# Sheet1.net
KiCad netlist of a schematic drawn in Altium Designer
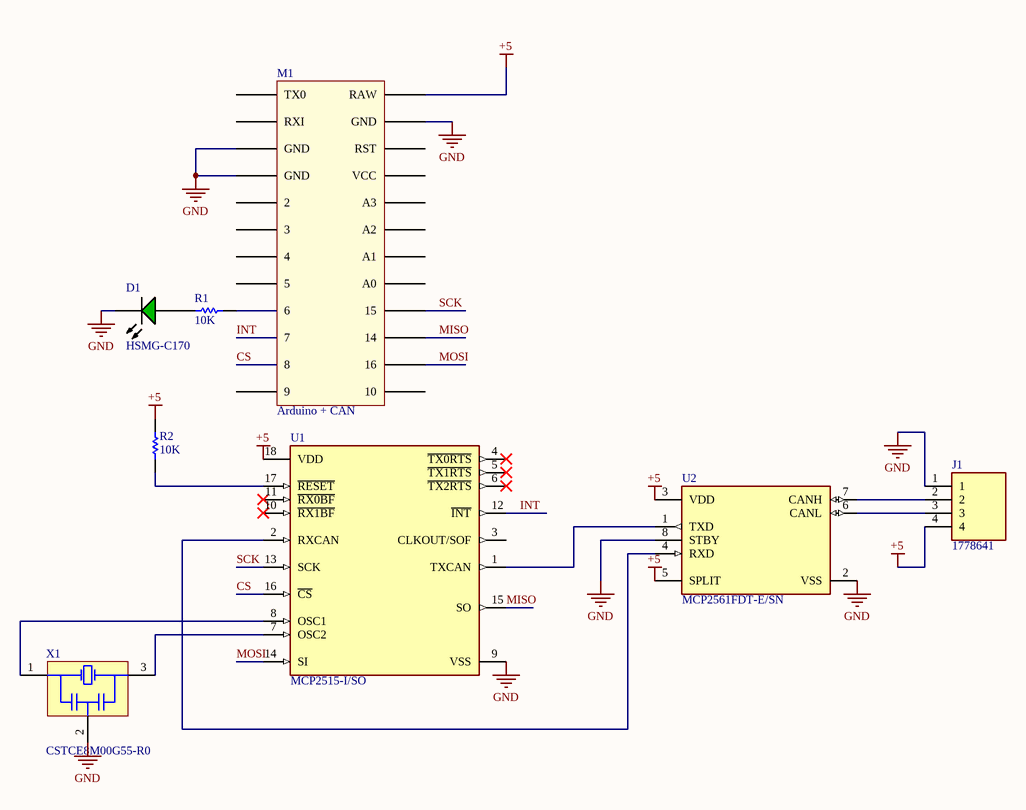
[diagram p0: Sheet1.SchDoc]

(export (version "E")
  (design (tool "Eeschema 10.0.6"))
  (components
    (comp (ref "D1")
      (value "HSMG-C170")
      (footprint "AVAG-HSMX-C170_V")
      (description "Chip LED, Green, 2.2 V, -40 to 85 degC, 2-Pin SMD, Pb-Free, Tape and Reel")
      (fields (field (name "MANUFACTURER") "Avago"))
      (libsource (lib "Altium Content Vault") (part "LED_GREEN_A1K2-2"))
    )
    (comp (ref "J1")
      (value "1778641")
      (footprint "SHDRRA4W60P0X250_1X4_1170X750X510P")
      (fields (field (name "MOUSER PART NUMBER") "651-1778641"))
      (libsource (lib "PTSM") (part "1778641"))
    )
    (comp (ref "M1")
      (value "Arduino + CAN")
      (footprint "PCBComponent_1")
      (description "Arduino Pro Micro + CAN Shield")
      (libsource (lib "Arduino") (part "Arduino"))
    )
    (comp (ref "R1")
      (value "10K")
      (footprint "RESC2013X50X30LL20T20")
      (fields (field (name "MANUFACTURER") "Vishay Dale") (field (name "PART NUMBER") "CRCW08050000Z0EA"))
      (libsource (lib "Altium Content Vault") (part "RES"))
    )
    (comp (ref "R2")
      (value "10K")
      (footprint "RESC2013X50X30LL20T20")
      (fields (field (name "MANUFACTURER") "Vishay Dale") (field (name "PART NUMBER") "CRCW08050000Z0EA"))
      (libsource (lib "Altium Content Vault") (part "RES"))
    )
    (comp (ref "U1")
      (value "MCP2515-I/SO")
      (footprint "FP-C04-051-MFG")
      (description "IC CAN CONTROLLER W/SPI 18SOIC")
      (fields
        (field (name "MANUFACTURER") "Microchip")
        (field (name "OCTOPART") "https://octopart.com/mcp2515-i%2Fso-microchip-430187")
      )
      (libsource (lib "Altium Content Vault") (part "1c78ea6ff576bac94664e2637e1b479"))
    )
    (comp (ref "U2")
      (value "MCP2561FDT-E/SN")
      (footprint "FP-C04-057-SN-MFG")
      (description "IC TRANSCEIVER 1/1 8SOIC")
      (libsource (lib "Altium Content Vault") (part "d629fcaead47a253bf8bf7df247dcfa"))
    )
    (comp (ref "X1")
      (value "CSTCE8M00G55-R0")
      (footprint "MURA-CSTCE_G_A-3_V")
      (description "Ceramic Resonator, 8 MHz, +/- 0.5%, -20 to 80 degC, 3-Pin SMD, RoHS, Tape and Reel")
      (fields (field (name "TOLERANCE") "0.5%") (field (name "MANUFACTURER") "Murata"))
      (libsource (lib "Altium Content Vault") (part "MURA-CSTCE_G_A-3"))
    )
  )
  (nets
    (net (code "1") (name "+5") (class "Default")
      (node (ref "J1") (pin "4") (pinfunction "4_4") (pintype "passive"))
      (node (ref "M1") (pin "24") (pinfunction "RAW_24") (pintype "passive"))
      (node (ref "R2") (pin "2") (pinfunction "2_2") (pintype "passive"))
      (node (ref "U1") (pin "18") (pinfunction "VDD_18") (pintype "power_in"))
      (node (ref "U2") (pin "3") (pinfunction "VDD_3") (pintype "power_in"))
      (node (ref "U2") (pin "5") (pinfunction "SPLIT_5") (pintype "passive"))
    )
    (net (code "2") (name "/CS") (class "Default")
      (node (ref "M1") (pin "11") (pinfunction "8_11") (pintype "passive"))
      (node (ref "U1") (pin "16") (pinfunction "~{CS}_16") (pintype "input"))
    )
    (net (code "3") (name "/INT") (class "Default")
      (node (ref "M1") (pin "10") (pinfunction "7_10") (pintype "passive"))
      (node (ref "U1") (pin "12") (pinfunction "~{INT}_12") (pintype "output"))
    )
    (net (code "4") (name "/MISO") (class "Default")
      (node (ref "M1") (pin "15") (pinfunction "14_15") (pintype "passive"))
      (node (ref "U1") (pin "15") (pinfunction "SO_15") (pintype "output"))
    )
    (net (code "5") (name "/MOSI") (class "Default")
      (node (ref "M1") (pin "14") (pinfunction "16_14") (pintype "passive"))
      (node (ref "U1") (pin "14") (pinfunction "SI_14") (pintype "input"))
    )
    (net (code "6") (name "/SCK") (class "Default")
      (node (ref "M1") (pin "16") (pinfunction "15_16") (pintype "passive"))
      (node (ref "U1") (pin "13") (pinfunction "SCK_13") (pintype "input"))
    )
    (net (code "7") (name "GND") (class "Default")
      (node (ref "D1") (pin "2") (pinfunction "K_2") (pintype "passive"))
      (node (ref "J1") (pin "1") (pinfunction "1_1") (pintype "passive"))
      (node (ref "M1") (pin "23") (pinfunction "GND_23") (pintype "passive"))
      (node (ref "M1") (pin "3") (pinfunction "GND_3") (pintype "passive"))
      (node (ref "M1") (pin "4") (pinfunction "GND_4") (pintype "passive"))
      (node (ref "U1") (pin "9") (pinfunction "VSS_9") (pintype "power_in"))
      (node (ref "U2") (pin "2") (pinfunction "VSS_2") (pintype "power_in"))
      (node (ref "U2") (pin "8") (pinfunction "STBY_8") (pintype "passive"))
      (node (ref "X1") (pin "2") (pinfunction "GND_2") (pintype "power_in"))
    )
    (net (code "8") (name "Net-(D1-A)") (class "Default")
      (node (ref "D1") (pin "1") (pinfunction "A_1") (pintype "passive"))
      (node (ref "R1") (pin "2") (pinfunction "2_2") (pintype "passive"))
    )
    (net (code "9") (name "Net-(M1-6)") (class "Default")
      (node (ref "M1") (pin "9") (pinfunction "6_9") (pintype "passive"))
      (node (ref "R1") (pin "1") (pinfunction "1_1") (pintype "passive"))
    )
    (net (code "10") (name "Net-(U1-OSC1)") (class "Default")
      (node (ref "U1") (pin "8") (pinfunction "OSC1_8") (pintype "input"))
      (node (ref "X1") (pin "1") (pinfunction "X1_1") (pintype "passive"))
    )
    (net (code "11") (name "Net-(U1-OSC2)") (class "Default")
      (node (ref "U1") (pin "7") (pinfunction "OSC2_7") (pintype "input"))
      (node (ref "X1") (pin "3") (pinfunction "X2_3") (pintype "passive"))
    )
    (net (code "12") (name "Net-(U1-RXCAN)") (class "Default")
      (node (ref "U1") (pin "2") (pinfunction "RXCAN_2") (pintype "input"))
      (node (ref "U2") (pin "4") (pinfunction "RXD_4") (pintype "input"))
    )
    (net (code "13") (name "Net-(U1-TXCAN)") (class "Default")
      (node (ref "U1") (pin "1") (pinfunction "TXCAN_1") (pintype "output"))
      (node (ref "U2") (pin "1") (pinfunction "TXD_1") (pintype "output"))
    )
    (net (code "14") (name "Net-(U1-~{RESET})") (class "Default")
      (node (ref "R2") (pin "1") (pinfunction "1_1") (pintype "passive"))
      (node (ref "U1") (pin "17") (pinfunction "~{RESET}_17") (pintype "input"))
    )
    (net (code "15") (name "Net-(U2-CANH)") (class "Default")
      (node (ref "J1") (pin "2") (pinfunction "2_2") (pintype "passive"))
      (node (ref "U2") (pin "7") (pinfunction "CANH_7") (pintype "bidirectional"))
    )
    (net (code "16") (name "Net-(U2-CANL)") (class "Default")
      (node (ref "J1") (pin "3") (pinfunction "3_3") (pintype "passive"))
      (node (ref "U2") (pin "6") (pinfunction "CANL_6") (pintype "bidirectional"))
    )
    (net (code "17") (name "unconnected-(M1-2-Pad5)") (class "Default")
      (node (ref "M1") (pin "5") (pinfunction "2_5") (pintype "passive"))
    )
    (net (code "18") (name "unconnected-(M1-3-Pad6)") (class "Default")
      (node (ref "M1") (pin "6") (pinfunction "3_6") (pintype "passive"))
    )
    (net (code "19") (name "unconnected-(M1-4-Pad7)") (class "Default")
      (node (ref "M1") (pin "7") (pinfunction "4_7") (pintype "passive"))
    )
    (net (code "20") (name "unconnected-(M1-5-Pad8)") (class "Default")
      (node (ref "M1") (pin "8") (pinfunction "5_8") (pintype "passive"))
    )
    (net (code "21") (name "unconnected-(M1-9-Pad12)") (class "Default")
      (node (ref "M1") (pin "12") (pinfunction "9_12") (pintype "passive"))
    )
    (net (code "22") (name "unconnected-(M1-10-Pad13)") (class "Default")
      (node (ref "M1") (pin "13") (pinfunction "10_13") (pintype "passive"))
    )
    (net (code "23") (name "unconnected-(M1-A0-Pad17)") (class "Default")
      (node (ref "M1") (pin "17") (pinfunction "A0_17") (pintype "passive"))
    )
    (net (code "24") (name "unconnected-(M1-A1-Pad18)") (class "Default")
      (node (ref "M1") (pin "18") (pinfunction "A1_18") (pintype "passive"))
    )
    (net (code "25") (name "unconnected-(M1-A2-Pad19)") (class "Default")
      (node (ref "M1") (pin "19") (pinfunction "A2_19") (pintype "passive"))
    )
    (net (code "26") (name "unconnected-(M1-A3-Pad20)") (class "Default")
      (node (ref "M1") (pin "20") (pinfunction "A3_20") (pintype "passive"))
    )
    (net (code "27") (name "unconnected-(M1-RST-Pad22)") (class "Default")
      (node (ref "M1") (pin "22") (pinfunction "RST_22") (pintype "passive"))
    )
    (net (code "28") (name "unconnected-(M1-RXI-Pad2)") (class "Default")
      (node (ref "M1") (pin "2") (pinfunction "RXI_2") (pintype "passive"))
    )
    (net (code "29") (name "unconnected-(M1-TX0-Pad1)") (class "Default")
      (node (ref "M1") (pin "1") (pinfunction "TX0_1") (pintype "passive"))
    )
    (net (code "30") (name "unconnected-(M1-VCC-Pad21)") (class "Default")
      (node (ref "M1") (pin "21") (pinfunction "VCC_21") (pintype "passive"))
    )
    (net (code "31") (name "unconnected-(U1-CLKOUT{slash}SOF-Pad3)") (class "Default")
      (node (ref "U1") (pin "3") (pinfunction "CLKOUT/SOF_3") (pintype "output"))
    )
    (net (code "32") (name "unconnected-(U1-~{RX0BF}-Pad11)") (class "Default")
      (node (ref "U1") (pin "11") (pinfunction "~{RX0BF}_11") (pintype "input+no_connect"))
    )
    (net (code "33") (name "unconnected-(U1-~{RX1BF}-Pad10)") (class "Default")
      (node (ref "U1") (pin "10") (pinfunction "~{RX1BF}_10") (pintype "input+no_connect"))
    )
    (net (code "34") (name "unconnected-(U1-~{TX0RTS}-Pad4)") (class "Default")
      (node (ref "U1") (pin "4") (pinfunction "~{TX0RTS}_4") (pintype "output+no_connect"))
    )
    (net (code "35") (name "unconnected-(U1-~{TX1RTS}-Pad5)") (class "Default")
      (node (ref "U1") (pin "5") (pinfunction "~{TX1RTS}_5") (pintype "output+no_connect"))
    )
    (net (code "36") (name "unconnected-(U1-~{TX2RTS}-Pad6)") (class "Default")
      (node (ref "U1") (pin "6") (pinfunction "~{TX2RTS}_6") (pintype "output+no_connect"))
    )
  )
)
